# Unibook_Breakout.net
KiCad netlist of a schematic drawn in EAGLE
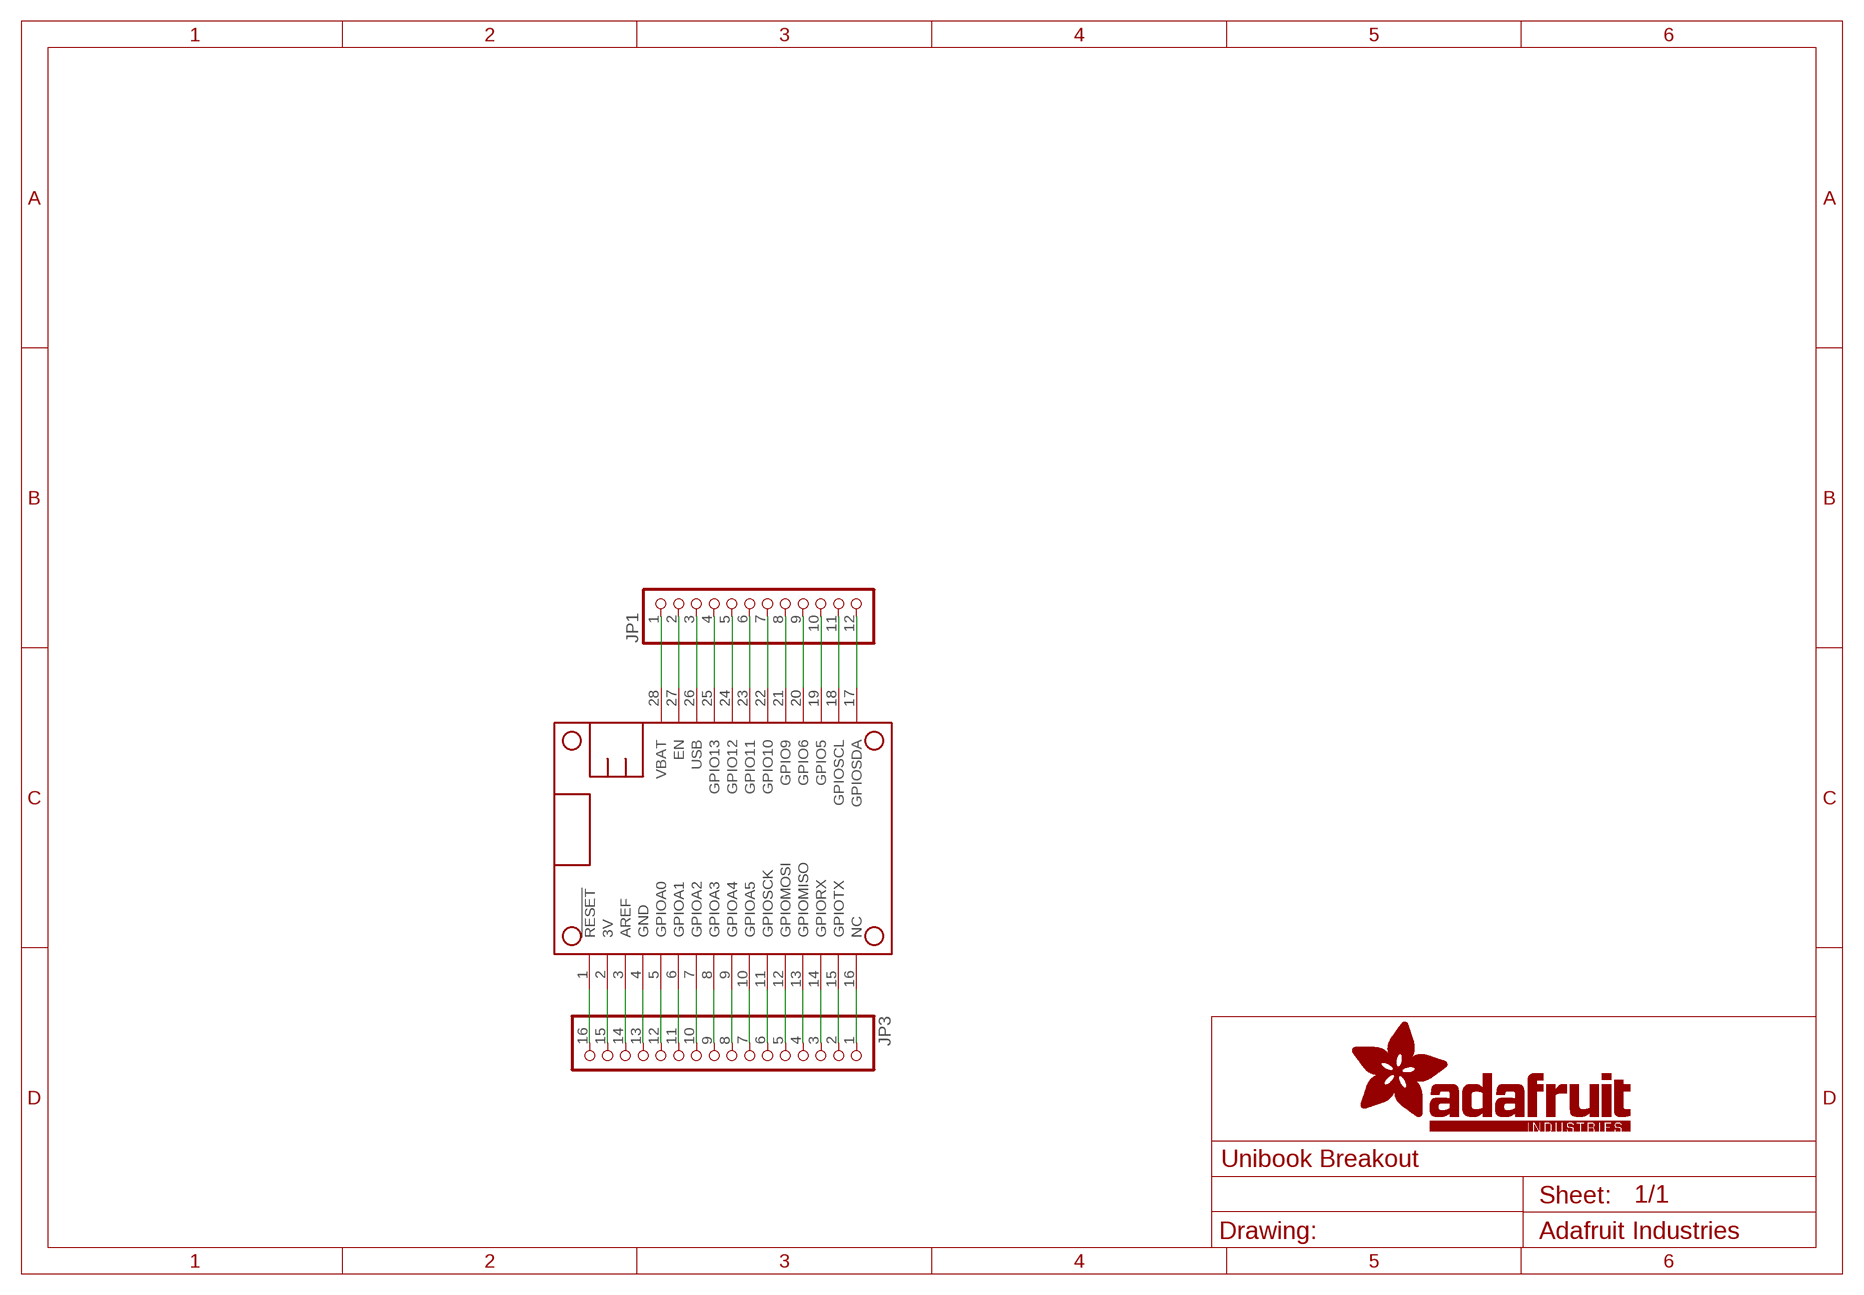
[diagram p0: schematic, sheet 1]

(export (version "E")
  (design (tool "Eeschema 10.0.6"))
  (components
    (comp (ref "JP1")
      (value "HEADER-1X1276MIL")
      (footprint "eagle-import:1X12_ROUND_76MIL")
      (libsource (lib "eagle-import") (part "HEADER-1X1276MIL"))
    )
    (comp (ref "JP3")
      (value "HEADER-1X16_76MIL")
      (footprint "eagle-import:1X16_ROUND_76MIL")
      (libsource (lib "eagle-import") (part "HEADER-1X16_76MIL"))
    )
    (comp (ref "MS1")
      (value "FEATHERWING")
      (footprint "eagle-import:FEATHERWING")
      (libsource (lib "eagle-import") (part "FEATHERWING"))
    )
  )
  (nets
    (net (code "1") (name "Net-(MS1-3V)") (class "Default")
      (node (ref "JP3") (pin "15") (pinfunction "15_15") (pintype "passive"))
      (node (ref "MS1") (pin "2") (pinfunction "3V_2") (pintype "power_in"))
    )
    (net (code "2") (name "Net-(MS1-AREF)") (class "Default")
      (node (ref "JP3") (pin "14") (pinfunction "14_14") (pintype "passive"))
      (node (ref "MS1") (pin "3") (pinfunction "AREF_3") (pintype "passive"))
    )
    (net (code "3") (name "Net-(MS1-EN)") (class "Default")
      (node (ref "JP1") (pin "2") (pinfunction "2_2") (pintype "passive"))
      (node (ref "MS1") (pin "27") (pinfunction "EN_27") (pintype "passive"))
    )
    (net (code "4") (name "Net-(MS1-GND)") (class "Default")
      (node (ref "JP3") (pin "13") (pinfunction "13_13") (pintype "passive"))
      (node (ref "MS1") (pin "4") (pinfunction "GND_4") (pintype "power_in"))
    )
    (net (code "5") (name "Net-(MS1-GPIO5)") (class "Default")
      (node (ref "JP1") (pin "10") (pinfunction "10_10") (pintype "passive"))
      (node (ref "MS1") (pin "19") (pinfunction "GPIO5_19") (pintype "bidirectional"))
    )
    (net (code "6") (name "Net-(MS1-GPIO6)") (class "Default")
      (node (ref "JP1") (pin "9") (pinfunction "9_9") (pintype "passive"))
      (node (ref "MS1") (pin "20") (pinfunction "GPIO6_20") (pintype "bidirectional"))
    )
    (net (code "7") (name "Net-(MS1-GPIO9)") (class "Default")
      (node (ref "JP1") (pin "8") (pinfunction "8_8") (pintype "passive"))
      (node (ref "MS1") (pin "21") (pinfunction "GPIO9_21") (pintype "bidirectional"))
    )
    (net (code "8") (name "Net-(MS1-GPIO10)") (class "Default")
      (node (ref "JP1") (pin "7") (pinfunction "7_7") (pintype "passive"))
      (node (ref "MS1") (pin "22") (pinfunction "GPIO10_22") (pintype "bidirectional"))
    )
    (net (code "9") (name "Net-(MS1-GPIO11)") (class "Default")
      (node (ref "JP1") (pin "6") (pinfunction "6_6") (pintype "passive"))
      (node (ref "MS1") (pin "23") (pinfunction "GPIO11_23") (pintype "bidirectional"))
    )
    (net (code "10") (name "Net-(MS1-GPIO12)") (class "Default")
      (node (ref "JP1") (pin "5") (pinfunction "5_5") (pintype "passive"))
      (node (ref "MS1") (pin "24") (pinfunction "GPIO12_24") (pintype "bidirectional"))
    )
    (net (code "11") (name "Net-(MS1-GPIO13)") (class "Default")
      (node (ref "JP1") (pin "4") (pinfunction "4_4") (pintype "passive"))
      (node (ref "MS1") (pin "25") (pinfunction "GPIO13_25") (pintype "bidirectional"))
    )
    (net (code "12") (name "Net-(MS1-GPIOA0)") (class "Default")
      (node (ref "JP3") (pin "12") (pinfunction "12_12") (pintype "passive"))
      (node (ref "MS1") (pin "5") (pinfunction "GPIOA0_5") (pintype "bidirectional"))
    )
    (net (code "13") (name "Net-(MS1-GPIOA1)") (class "Default")
      (node (ref "JP3") (pin "11") (pinfunction "11_11") (pintype "passive"))
      (node (ref "MS1") (pin "6") (pinfunction "GPIOA1_6") (pintype "bidirectional"))
    )
    (net (code "14") (name "Net-(MS1-GPIOA2)") (class "Default")
      (node (ref "JP3") (pin "10") (pinfunction "10_10") (pintype "passive"))
      (node (ref "MS1") (pin "7") (pinfunction "GPIOA2_7") (pintype "bidirectional"))
    )
    (net (code "15") (name "Net-(MS1-GPIOA3)") (class "Default")
      (node (ref "JP3") (pin "9") (pinfunction "9_9") (pintype "passive"))
      (node (ref "MS1") (pin "8") (pinfunction "GPIOA3_8") (pintype "bidirectional"))
    )
    (net (code "16") (name "Net-(MS1-GPIOA4)") (class "Default")
      (node (ref "JP3") (pin "8") (pinfunction "8_8") (pintype "passive"))
      (node (ref "MS1") (pin "9") (pinfunction "GPIOA4_9") (pintype "bidirectional"))
    )
    (net (code "17") (name "Net-(MS1-GPIOA5)") (class "Default")
      (node (ref "JP3") (pin "7") (pinfunction "7_7") (pintype "passive"))
      (node (ref "MS1") (pin "10") (pinfunction "GPIOA5_10") (pintype "bidirectional"))
    )
    (net (code "18") (name "Net-(MS1-GPIOMISO)") (class "Default")
      (node (ref "JP3") (pin "4") (pinfunction "4_4") (pintype "passive"))
      (node (ref "MS1") (pin "13") (pinfunction "GPIOMISO_13") (pintype "bidirectional"))
    )
    (net (code "19") (name "Net-(MS1-GPIOMOSI)") (class "Default")
      (node (ref "JP3") (pin "5") (pinfunction "5_5") (pintype "passive"))
      (node (ref "MS1") (pin "12") (pinfunction "GPIOMOSI_12") (pintype "bidirectional"))
    )
    (net (code "20") (name "Net-(MS1-GPIORX)") (class "Default")
      (node (ref "JP3") (pin "3") (pinfunction "3_3") (pintype "passive"))
      (node (ref "MS1") (pin "14") (pinfunction "GPIORX_14") (pintype "bidirectional"))
    )
    (net (code "21") (name "Net-(MS1-GPIOSCK)") (class "Default")
      (node (ref "JP3") (pin "6") (pinfunction "6_6") (pintype "passive"))
      (node (ref "MS1") (pin "11") (pinfunction "GPIOSCK_11") (pintype "bidirectional"))
    )
    (net (code "22") (name "Net-(MS1-GPIOSCL)") (class "Default")
      (node (ref "JP1") (pin "11") (pinfunction "11_11") (pintype "passive"))
      (node (ref "MS1") (pin "18") (pinfunction "GPIOSCL_18") (pintype "bidirectional"))
    )
    (net (code "23") (name "Net-(MS1-GPIOSDA)") (class "Default")
      (node (ref "JP1") (pin "12") (pinfunction "12_12") (pintype "passive"))
      (node (ref "MS1") (pin "17") (pinfunction "GPIOSDA_17") (pintype "bidirectional"))
    )
    (net (code "24") (name "Net-(MS1-GPIOTX)") (class "Default")
      (node (ref "JP3") (pin "2") (pinfunction "2_2") (pintype "passive"))
      (node (ref "MS1") (pin "15") (pinfunction "GPIOTX_15") (pintype "bidirectional"))
    )
    (net (code "25") (name "Net-(MS1-NC)") (class "Default")
      (node (ref "JP3") (pin "1") (pinfunction "1_1") (pintype "passive"))
      (node (ref "MS1") (pin "16") (pinfunction "NC_16") (pintype "passive"))
    )
    (net (code "26") (name "Net-(MS1-USB)") (class "Default")
      (node (ref "JP1") (pin "3") (pinfunction "3_3") (pintype "passive"))
      (node (ref "MS1") (pin "26") (pinfunction "USB_26") (pintype "power_in"))
    )
    (net (code "27") (name "Net-(MS1-VBAT)") (class "Default")
      (node (ref "JP1") (pin "1") (pinfunction "1_1") (pintype "passive"))
      (node (ref "MS1") (pin "28") (pinfunction "VBAT_28") (pintype "power_in"))
    )
    (net (code "28") (name "Net-(MS1-~{RESET})") (class "Default")
      (node (ref "JP3") (pin "16") (pinfunction "16_16") (pintype "passive"))
      (node (ref "MS1") (pin "1") (pinfunction "~{RESET}_1") (pintype "input"))
    )
  )
)
